# 14audio.net
KiCad netlist of a schematic drawn in Altium Designer
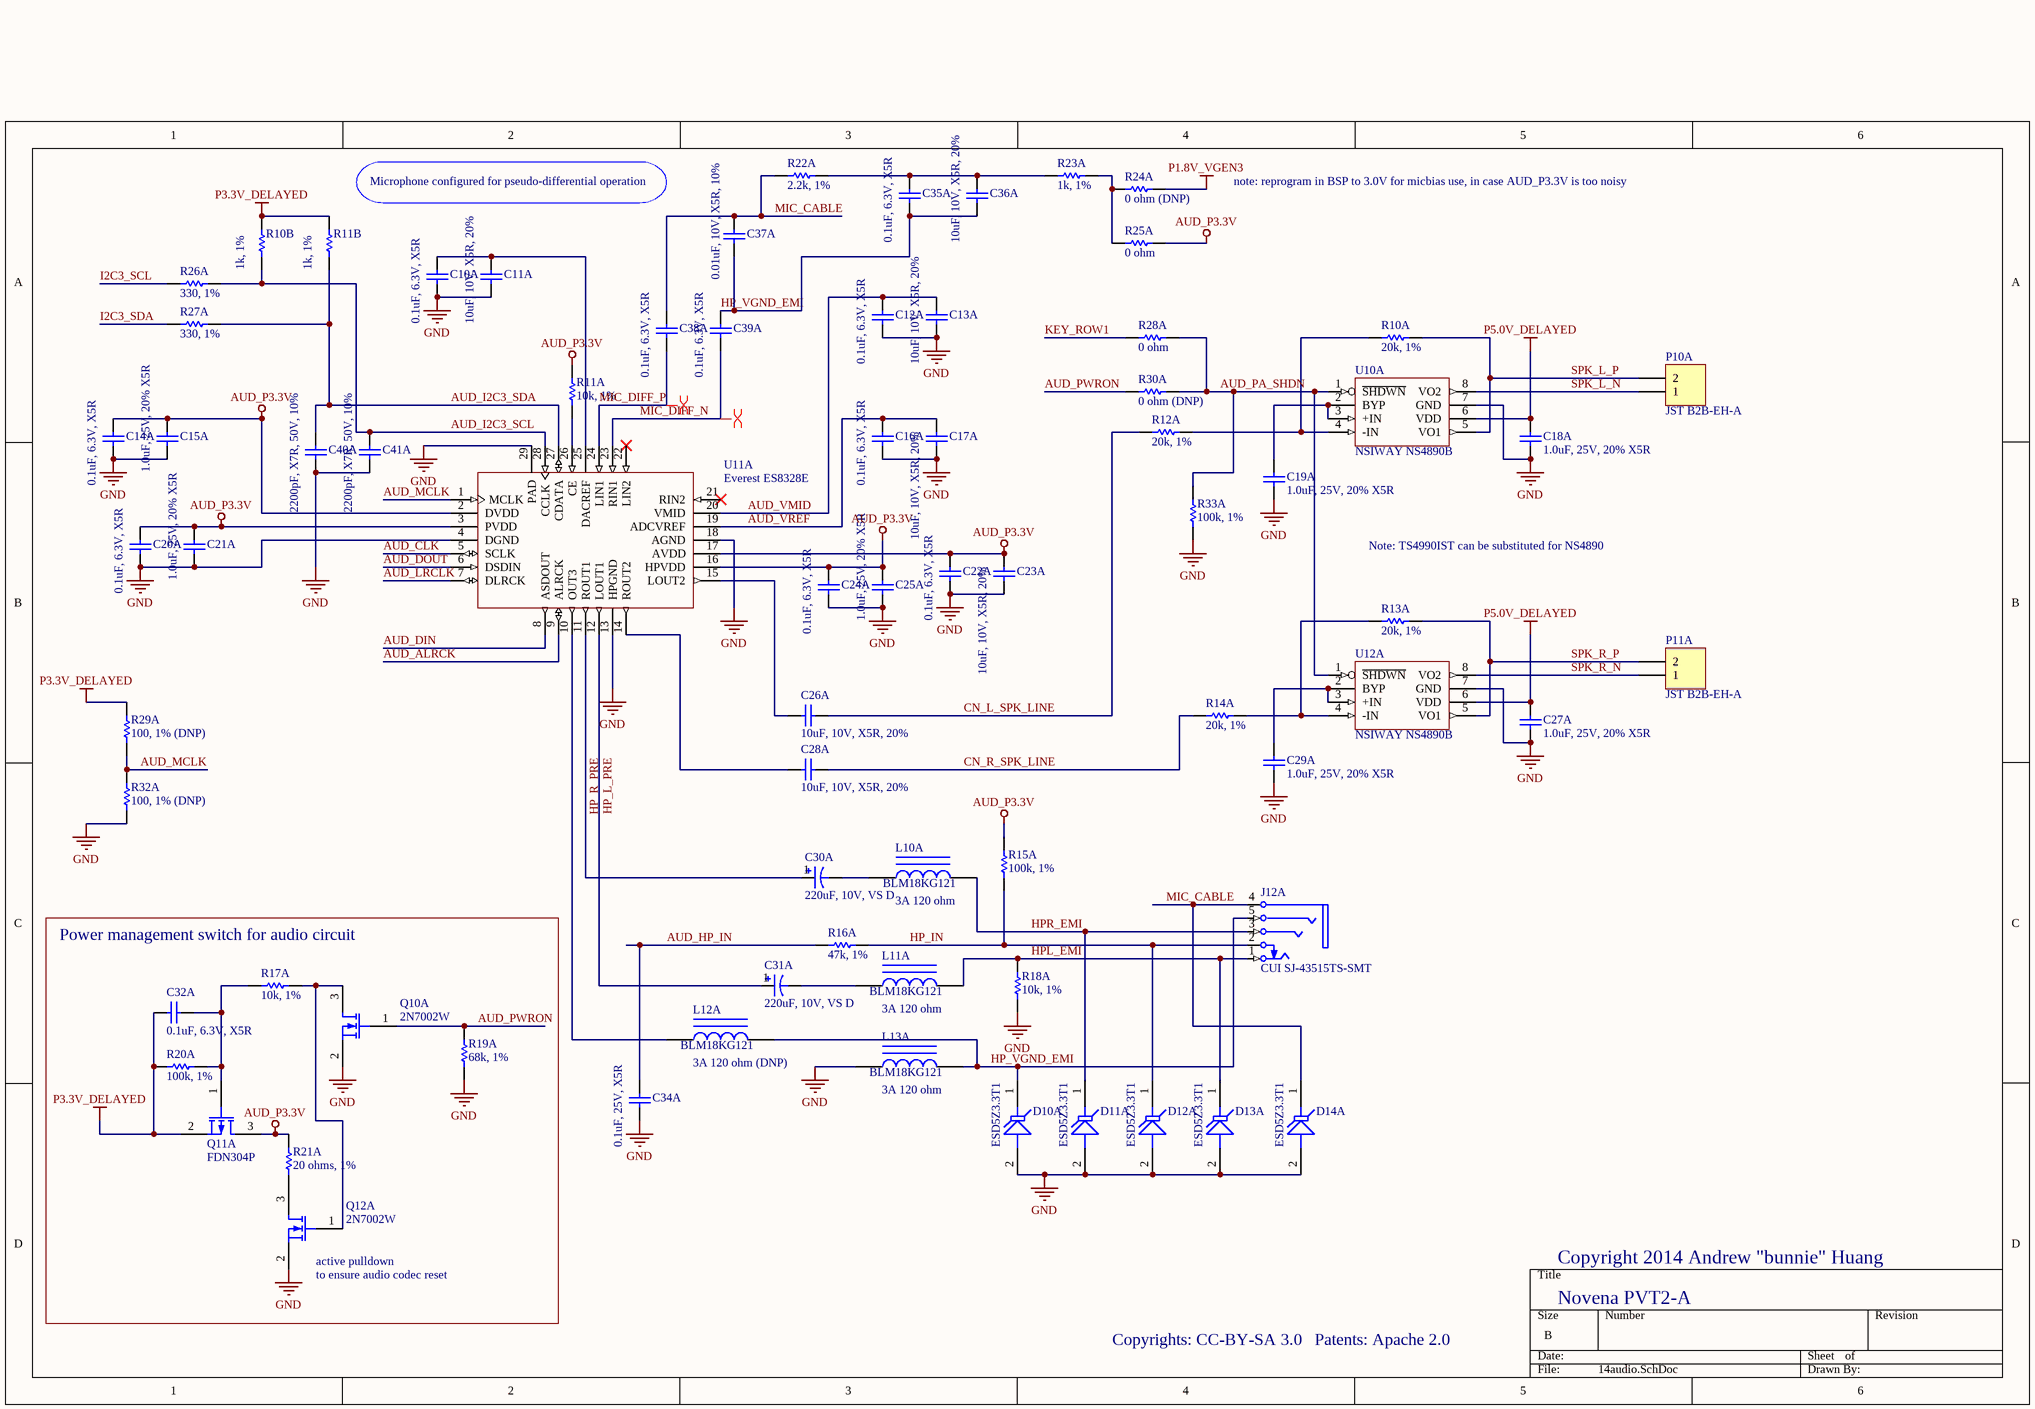
[diagram p0: 14audio.SchDoc]

(export (version "E")
  (design (tool "Eeschema 10.0.6"))
  (components
    (comp (ref "C10A")
      (value "0.1uF, 6.3V, X5R")
      (footprint "CAPC0603N_B")
      (description "Capacitor (Semiconductor SIM Model)")
      (fields (field (name "PUBLISHER") "Altium Limited"))
      (libsource (lib "Miscellaneous Devices") (part "Cap Semi"))
    )
    (comp (ref "C11A")
      (value "10uF, 10V, X5R, 20%")
      (footprint "CAPC1608N")
      (description "Capacitor (Semiconductor SIM Model)")
      (fields (field (name "PUBLISHER") "Altium Limited"))
      (libsource (lib "Miscellaneous Devices") (part "Cap Semi"))
    )
    (comp (ref "C12A")
      (value "0.1uF, 6.3V, X5R")
      (footprint "CAPC0603N_B")
      (description "Capacitor (Semiconductor SIM Model)")
      (fields (field (name "PUBLISHER") "Altium Limited"))
      (libsource (lib "Miscellaneous Devices") (part "Cap Semi"))
    )
    (comp (ref "C13A")
      (value "10uF, 10V, X5R, 20%")
      (footprint "CAPC1608N")
      (description "Capacitor (Semiconductor SIM Model)")
      (fields (field (name "PUBLISHER") "Altium Limited"))
      (libsource (lib "Miscellaneous Devices") (part "Cap Semi"))
    )
    (comp (ref "C14A")
      (value "0.1uF, 6.3V, X5R")
      (footprint "CAPC0603N_B")
      (description "Capacitor (Semiconductor SIM Model)")
      (fields (field (name "PUBLISHER") "Altium Limited"))
      (libsource (lib "Miscellaneous Devices") (part "Cap Semi"))
    )
    (comp (ref "C15A")
      (value "1.0uF, 25V, 20% X5R")
      (footprint "CAPC1608N")
      (description "Capacitor (Semiconductor SIM Model)")
      (fields (field (name "PUBLISHER") "Altium Limited"))
      (libsource (lib "Miscellaneous Devices") (part "Cap Semi"))
    )
    (comp (ref "C16A")
      (value "0.1uF, 6.3V, X5R")
      (footprint "CAPC0603N_B")
      (description "Capacitor (Semiconductor SIM Model)")
      (fields (field (name "PUBLISHER") "Altium Limited"))
      (libsource (lib "Miscellaneous Devices") (part "Cap Semi"))
    )
    (comp (ref "C17A")
      (value "10uF, 10V, X5R, 20%")
      (footprint "CAPC1608N")
      (description "Capacitor (Semiconductor SIM Model)")
      (fields (field (name "PUBLISHER") "Altium Limited"))
      (libsource (lib "Miscellaneous Devices") (part "Cap Semi"))
    )
    (comp (ref "C18A")
      (value "1.0uF, 25V, 20% X5R")
      (footprint "CAPC1608N")
      (description "Capacitor (Semiconductor SIM Model)")
      (fields (field (name "PUBLISHER") "Altium Limited"))
      (libsource (lib "Miscellaneous Devices") (part "Cap Semi"))
    )
    (comp (ref "C19A")
      (value "1.0uF, 25V, 20% X5R")
      (footprint "CAPC1608N")
      (description "Capacitor (Semiconductor SIM Model)")
      (fields (field (name "PUBLISHER") "Altium Limited"))
      (libsource (lib "Miscellaneous Devices") (part "Cap Semi"))
    )
    (comp (ref "C20A")
      (value "0.1uF, 6.3V, X5R")
      (footprint "CAPC0603N_B")
      (description "Capacitor (Semiconductor SIM Model)")
      (fields (field (name "PUBLISHER") "Altium Limited"))
      (libsource (lib "Miscellaneous Devices") (part "Cap Semi"))
    )
    (comp (ref "C21A")
      (value "1.0uF, 25V, 20% X5R")
      (footprint "CAPC1608N")
      (description "Capacitor (Semiconductor SIM Model)")
      (fields (field (name "PUBLISHER") "Altium Limited"))
      (libsource (lib "Miscellaneous Devices") (part "Cap Semi"))
    )
    (comp (ref "C22A")
      (value "0.1uF, 6.3V, X5R")
      (footprint "CAPC0603N_B")
      (description "Capacitor (Semiconductor SIM Model)")
      (fields (field (name "PUBLISHER") "Altium Limited"))
      (libsource (lib "Miscellaneous Devices") (part "Cap Semi"))
    )
    (comp (ref "C23A")
      (value "10uF, 10V, X5R, 20%")
      (footprint "CAPC1608N")
      (description "Capacitor (Semiconductor SIM Model)")
      (fields (field (name "PUBLISHER") "Altium Limited"))
      (libsource (lib "Miscellaneous Devices") (part "Cap Semi"))
    )
    (comp (ref "C24A")
      (value "0.1uF, 6.3V, X5R")
      (footprint "CAPC0603N_B")
      (description "Capacitor (Semiconductor SIM Model)")
      (fields (field (name "PUBLISHER") "Altium Limited"))
      (libsource (lib "Miscellaneous Devices") (part "Cap Semi"))
    )
    (comp (ref "C25A")
      (value "1.0uF, 25V, 20% X5R")
      (footprint "CAPC1608N")
      (description "Capacitor (Semiconductor SIM Model)")
      (fields (field (name "PUBLISHER") "Altium Limited"))
      (libsource (lib "Miscellaneous Devices") (part "Cap Semi"))
    )
    (comp (ref "C26A")
      (value "10uF, 10V, X5R, 20%")
      (footprint "CAPC1608N")
      (description "Capacitor (Semiconductor SIM Model)")
      (fields (field (name "PUBLISHER") "Altium Limited"))
      (libsource (lib "Miscellaneous Devices") (part "Cap Semi"))
    )
    (comp (ref "C27A")
      (value "1.0uF, 25V, 20% X5R")
      (footprint "CAPC1608N")
      (description "Capacitor (Semiconductor SIM Model)")
      (fields (field (name "PUBLISHER") "Altium Limited"))
      (libsource (lib "Miscellaneous Devices") (part "Cap Semi"))
    )
    (comp (ref "C28A")
      (value "10uF, 10V, X5R, 20%")
      (footprint "CAPC1608N")
      (description "Capacitor (Semiconductor SIM Model)")
      (fields (field (name "PUBLISHER") "Altium Limited"))
      (libsource (lib "Miscellaneous Devices") (part "Cap Semi"))
    )
    (comp (ref "C29A")
      (value "1.0uF, 25V, 20% X5R")
      (footprint "CAPC1608N")
      (description "Capacitor (Semiconductor SIM Model)")
      (fields (field (name "PUBLISHER") "Altium Limited"))
      (libsource (lib "Miscellaneous Devices") (part "Cap Semi"))
    )
    (comp (ref "C30A")
      (value "220uF, 10V, VS D")
      (footprint "6004pcb:ALCAP_D")
      (description "Polarized Capacitor (Surface Mount)")
      (fields (field (name "PUBLISHER") "Altium Limited"))
      (libsource (lib "Miscellaneous Devices") (part "Cap Pol3"))
    )
    (comp (ref "C31A")
      (value "220uF, 10V, VS D")
      (footprint "6004pcb:ALCAP_D")
      (description "Polarized Capacitor (Surface Mount)")
      (fields (field (name "PUBLISHER") "Altium Limited"))
      (libsource (lib "Miscellaneous Devices") (part "Cap Pol3"))
    )
    (comp (ref "C32A")
      (value "0.1uF, 6.3V, X5R")
      (footprint "CAPC0603N_B")
      (description "Capacitor (Semiconductor SIM Model)")
      (fields (field (name "PUBLISHER") "Altium Limited"))
      (libsource (lib "Miscellaneous Devices") (part "Cap Semi"))
    )
    (comp (ref "C34A")
      (value "0.1uF, 25V, X5R")
      (footprint "CAPC1005N")
      (description "Capacitor (Semiconductor SIM Model)")
      (fields (field (name "PUBLISHER") "Altium Limited"))
      (libsource (lib "Miscellaneous Devices") (part "Cap Semi"))
    )
    (comp (ref "C35A")
      (value "0.1uF, 6.3V, X5R")
      (footprint "CAPC0603N_B")
      (description "Capacitor (Semiconductor SIM Model)")
      (fields (field (name "PUBLISHER") "Altium Limited"))
      (libsource (lib "Miscellaneous Devices") (part "Cap Semi"))
    )
    (comp (ref "C36A")
      (value "10uF, 10V, X5R, 20%")
      (footprint "CAPC1608N")
      (description "Capacitor (Semiconductor SIM Model)")
      (fields (field (name "PUBLISHER") "Altium Limited"))
      (libsource (lib "Miscellaneous Devices") (part "Cap Semi"))
    )
    (comp (ref "C37A")
      (value "0.01uF, 10V, X5R, 10%")
      (footprint "CAPC0603N_B")
      (description "Capacitor (Semiconductor SIM Model)")
      (fields (field (name "PUBLISHER") "Altium Limited"))
      (libsource (lib "Miscellaneous Devices") (part "Cap Semi"))
    )
    (comp (ref "C38A")
      (value "0.1uF, 6.3V, X5R")
      (footprint "CAPC0603N_B")
      (description "Capacitor (Semiconductor SIM Model)")
      (fields (field (name "PUBLISHER") "Altium Limited"))
      (libsource (lib "Miscellaneous Devices") (part "Cap Semi"))
    )
    (comp (ref "C39A")
      (value "0.1uF, 6.3V, X5R")
      (footprint "CAPC0603N_B")
      (description "Capacitor (Semiconductor SIM Model)")
      (fields (field (name "PUBLISHER") "Altium Limited"))
      (libsource (lib "Miscellaneous Devices") (part "Cap Semi"))
    )
    (comp (ref "C40A")
      (value "2200pF, X7R, 50V, 10%")
      (footprint "CAPC1005N")
      (description "Capacitor (Semiconductor SIM Model)")
      (fields (field (name "PUBLISHER") "Altium Limited"))
      (libsource (lib "Miscellaneous Devices") (part "Cap Semi"))
    )
    (comp (ref "C41A")
      (value "2200pF, X7R, 50V, 10%")
      (footprint "CAPC1005N")
      (description "Capacitor (Semiconductor SIM Model)")
      (fields (field (name "PUBLISHER") "Altium Limited"))
      (libsource (lib "Miscellaneous Devices") (part "Cap Semi"))
    )
    (comp (ref "D10A")
      (value "ESD5Z3.3T1")
      (footprint "SOD-523")
      (description "On Semi 3.3V standoff TVS diode")
      (fields (field (name "PUBLISHER") "Altium Limited"))
      (libsource (lib "Miscellaneous Devices") (part "Tranzorb"))
    )
    (comp (ref "D11A")
      (value "ESD5Z3.3T1")
      (footprint "SOD-523")
      (description "On Semi 3.3V standoff TVS diode")
      (fields (field (name "PUBLISHER") "Altium Limited"))
      (libsource (lib "Miscellaneous Devices") (part "Tranzorb"))
    )
    (comp (ref "D12A")
      (value "ESD5Z3.3T1")
      (footprint "SOD-523")
      (description "On Semi 3.3V standoff TVS diode")
      (fields (field (name "PUBLISHER") "Altium Limited"))
      (libsource (lib "Miscellaneous Devices") (part "Tranzorb"))
    )
    (comp (ref "D13A")
      (value "ESD5Z3.3T1")
      (footprint "SOD-523")
      (description "On Semi 3.3V standoff TVS diode")
      (fields (field (name "PUBLISHER") "Altium Limited"))
      (libsource (lib "Miscellaneous Devices") (part "Tranzorb"))
    )
    (comp (ref "D14A")
      (value "ESD5Z3.3T1")
      (footprint "SOD-523")
      (description "On Semi 3.3V standoff TVS diode")
      (fields (field (name "PUBLISHER") "Altium Limited"))
      (libsource (lib "Miscellaneous Devices") (part "Tranzorb"))
    )
    (comp (ref "J12A")
      (value "CUI SJ-43515TS-SMT")
      (footprint "CUI_SJ_43515TS-SMT")
      (description "Jack Socket, 3.5mm, SMT, 4-conductor")
      (fields (field (name "PUBLISHER") "Altium Limited"))
      (libsource (lib "commonsch") (part "Phonejack4 TN"))
    )
    (comp (ref "L10A")
      (value "BLM18KG121")
      (footprint "INDC1608AN")
      (description "Magnetic-Core Inductor")
      (fields (field (name "ALTIUM_VALUE") "3A 120 ohm") (field (name "PUBLISHER") "Altium Limited"))
      (libsource (lib "Miscellaneous Devices") (part "Inductor Iron"))
    )
    (comp (ref "L11A")
      (value "BLM18KG121")
      (footprint "INDC1608AN")
      (description "Magnetic-Core Inductor")
      (fields (field (name "ALTIUM_VALUE") "3A 120 ohm") (field (name "PUBLISHER") "Altium Limited"))
      (libsource (lib "Miscellaneous Devices") (part "Inductor Iron"))
    )
    (comp (ref "L12A")
      (value "BLM18KG121")
      (footprint "INDC1608AN")
      (description "Magnetic-Core Inductor")
      (fields (field (name "ALTIUM_VALUE") "3A 120 ohm (DNP)") (field (name "PUBLISHER") "Altium Limited"))
      (libsource (lib "Miscellaneous Devices") (part "Inductor Iron"))
    )
    (comp (ref "L13A")
      (value "BLM18KG121")
      (footprint "INDC1608AN")
      (description "Magnetic-Core Inductor")
      (fields (field (name "ALTIUM_VALUE") "3A 120 ohm") (field (name "PUBLISHER") "Altium Limited"))
      (libsource (lib "Miscellaneous Devices") (part "Inductor Iron"))
    )
    (comp (ref "P10A")
      (value "JST B2B-EH-A")
      (footprint "JST_B2B_EH_A")
      (description "Header, 2-Pin")
      (fields (field (name "PUBLISHER") "Altium Limited"))
      (libsource (lib "Miscellaneous Connectors") (part "Header 2"))
    )
    (comp (ref "P11A")
      (value "JST B2B-EH-A")
      (footprint "JST_B2B_EH_A")
      (description "Header, 2-Pin")
      (fields (field (name "PUBLISHER") "Altium Limited"))
      (libsource (lib "Miscellaneous Connectors") (part "Header 2"))
    )
    (comp (ref "Q10A")
      (value "2N7002W")
      (footprint "SOT323-3AN")
      (description "N-Channel MOSFET")
      (fields (field (name "PUBLISHER") "Altium Limited"))
      (libsource (lib "Miscellaneous Devices") (part "MOSFET-N"))
    )
    (comp (ref "Q11A")
      (value "FDN304P")
      (footprint "SOT23-3N")
      (description "P-Channel MOSFET")
      (fields (field (name "PUBLISHER") "Altium Limited"))
      (libsource (lib "Miscellaneous Devices") (part "MOSFET-P"))
    )
    (comp (ref "Q12A")
      (value "2N7002W")
      (footprint "SOT323-3AN")
      (description "N-Channel MOSFET")
      (fields (field (name "PUBLISHER") "Altium Limited"))
      (libsource (lib "Miscellaneous Devices") (part "MOSFET-N"))
    )
    (comp (ref "R10A")
      (value "20k, 1%")
      (footprint "RESC1005N")
      (description "Resistor")
      (fields (field (name "PUBLISHER") "Altium Limited"))
      (libsource (lib "Miscellaneous Devices") (part "Res1"))
    )
    (comp (ref "R10B")
      (value "1k, 1%")
      (footprint "RESC1005N")
      (description "Resistor")
      (fields (field (name "PUBLISHER") "Altium Limited"))
      (libsource (lib "Miscellaneous Devices") (part "Res1"))
    )
    (comp (ref "R11A")
      (value "10k, 1%")
      (footprint "RESC1005N")
      (description "Resistor")
      (fields (field (name "PUBLISHER") "Altium Limited"))
      (libsource (lib "Miscellaneous Devices") (part "Res1"))
    )
    (comp (ref "R11B")
      (value "1k, 1%")
      (footprint "RESC1005N")
      (description "Resistor")
      (fields (field (name "PUBLISHER") "Altium Limited"))
      (libsource (lib "Miscellaneous Devices") (part "Res1"))
    )
    (comp (ref "R12A")
      (value "20k, 1%")
      (footprint "RESC1005N")
      (description "Resistor")
      (fields (field (name "PUBLISHER") "Altium Limited"))
      (libsource (lib "Miscellaneous Devices") (part "Res1"))
    )
    (comp (ref "R13A")
      (value "20k, 1%")
      (footprint "RESC1005N")
      (description "Resistor")
      (fields (field (name "PUBLISHER") "Altium Limited"))
      (libsource (lib "Miscellaneous Devices") (part "Res1"))
    )
    (comp (ref "R14A")
      (value "20k, 1%")
      (footprint "RESC1005N")
      (description "Resistor")
      (fields (field (name "PUBLISHER") "Altium Limited"))
      (libsource (lib "Miscellaneous Devices") (part "Res1"))
    )
    (comp (ref "R15A")
      (value "100k, 1%")
      (footprint "RESC1005N")
      (description "Resistor")
      (fields (field (name "PUBLISHER") "Altium Limited"))
      (libsource (lib "Miscellaneous Devices") (part "Res1"))
    )
    (comp (ref "R16A")
      (value "47k, 1%")
      (footprint "RESC1005N")
      (description "Resistor")
      (fields (field (name "PUBLISHER") "Altium Limited"))
      (libsource (lib "Miscellaneous Devices") (part "Res1"))
    )
    (comp (ref "R17A")
      (value "10k, 1%")
      (footprint "RESC1005N")
      (description "Resistor")
      (fields (field (name "PUBLISHER") "Altium Limited"))
      (libsource (lib "Miscellaneous Devices") (part "Res1"))
    )
    (comp (ref "R18A")
      (value "10k, 1%")
      (footprint "RESC1005N")
      (description "Resistor")
      (fields (field (name "PUBLISHER") "Altium Limited"))
      (libsource (lib "Miscellaneous Devices") (part "Res1"))
    )
    (comp (ref "R19A")
      (value "68k, 1%")
      (footprint "RESC1005N")
      (description "Resistor")
      (fields (field (name "PUBLISHER") "Altium Limited"))
      (libsource (lib "Miscellaneous Devices") (part "Res1"))
    )
    (comp (ref "R20A")
      (value "100k, 1%")
      (footprint "RESC1005N")
      (description "Resistor")
      (fields (field (name "PUBLISHER") "Altium Limited"))
      (libsource (lib "Miscellaneous Devices") (part "Res1"))
    )
    (comp (ref "R21A")
      (value "20 ohms, 1%")
      (footprint "RESC1005N")
      (description "Resistor")
      (fields (field (name "PUBLISHER") "Altium Limited"))
      (libsource (lib "Miscellaneous Devices") (part "Res1"))
    )
    (comp (ref "R22A")
      (value "2.2k, 1%")
      (footprint "RESC1005N")
      (description "Resistor")
      (fields (field (name "PUBLISHER") "Altium Limited"))
      (libsource (lib "Miscellaneous Devices") (part "Res1"))
    )
    (comp (ref "R23A")
      (value "1k, 1%")
      (footprint "RESC1005N")
      (description "Resistor")
      (fields (field (name "PUBLISHER") "Altium Limited"))
      (libsource (lib "Miscellaneous Devices") (part "Res1"))
    )
    (comp (ref "R24A")
      (value "0 ohm (DNP)")
      (footprint "RESC1005N")
      (description "Resistor")
      (fields (field (name "PUBLISHER") "Altium Limited"))
      (libsource (lib "Miscellaneous Devices") (part "Res1"))
    )
    (comp (ref "R25A")
      (value "0 ohm")
      (footprint "RESC1005N")
      (description "Resistor")
      (fields (field (name "PUBLISHER") "Altium Limited"))
      (libsource (lib "Miscellaneous Devices") (part "Res1"))
    )
    (comp (ref "R26A")
      (value "330, 1%")
      (footprint "RESC1005N")
      (description "Resistor")
      (fields (field (name "PUBLISHER") "Altium Limited"))
      (libsource (lib "Miscellaneous Devices") (part "Res1"))
    )
    (comp (ref "R27A")
      (value "330, 1%")
      (footprint "RESC1005N")
      (description "Resistor")
      (fields (field (name "PUBLISHER") "Altium Limited"))
      (libsource (lib "Miscellaneous Devices") (part "Res1"))
    )
    (comp (ref "R28A")
      (value "0 ohm")
      (footprint "RESC1005N")
      (description "Resistor")
      (fields (field (name "PUBLISHER") "Altium Limited"))
      (libsource (lib "Miscellaneous Devices") (part "Res1"))
    )
    (comp (ref "R29A")
      (value "100, 1% (DNP)")
      (footprint "RESC1005N")
      (description "Resistor")
      (fields (field (name "PUBLISHER") "Altium Limited"))
      (libsource (lib "Miscellaneous Devices") (part "Res1"))
    )
    (comp (ref "R30A")
      (value "0 ohm (DNP)")
      (footprint "RESC1005N")
      (description "Resistor")
      (fields (field (name "PUBLISHER") "Altium Limited"))
      (libsource (lib "Miscellaneous Devices") (part "Res1"))
    )
    (comp (ref "R32A")
      (value "100, 1% (DNP)")
      (footprint "RESC1005N")
      (description "Resistor")
      (fields (field (name "PUBLISHER") "Altium Limited"))
      (libsource (lib "Miscellaneous Devices") (part "Res1"))
    )
    (comp (ref "R33A")
      (value "100k, 1%")
      (footprint "RESC1005N")
      (description "Resistor")
      (fields (field (name "PUBLISHER") "Altium Limited"))
      (libsource (lib "Miscellaneous Devices") (part "Res1"))
    )
    (comp (ref "U10A")
      (value "NSIWAY NS4890B")
      (footprint "MSOP8")
      (description "1W 8 ohm low-cost amplifier")
      (libsource (lib "commonsch") (part "NSIWAY_NS4890"))
    )
    (comp (ref "U11A")
      (value "Everest ES8328E")
      (footprint "QFN50P500X500-28V1N")
      (description "Low-cost audio CODEC by Everest")
      (libsource (lib "commonsch") (part "Everest_ES8328"))
    )
    (comp (ref "U12A")
      (value "NSIWAY NS4890B")
      (footprint "MSOP8")
      (description "1W 8 ohm low-cost amplifier")
      (libsource (lib "commonsch") (part "NSIWAY_NS4890"))
    )
  )
  (nets
    (net (code "1") (name "/AUD_ALRCK") (class "Default")
      (node (ref "U11A") (pin "9") (pinfunction "ALRCK_9") (pintype "bidirectional"))
    )
    (net (code "2") (name "/AUD_CLK") (class "Default")
      (node (ref "U11A") (pin "5") (pinfunction "SCLK_5") (pintype "bidirectional"))
    )
    (net (code "3") (name "/AUD_DIN") (class "Default")
      (node (ref "U11A") (pin "8") (pinfunction "ASDOUT_8") (pintype "output"))
    )
    (net (code "4") (name "/AUD_DOUT") (class "Default")
      (node (ref "U11A") (pin "6") (pinfunction "DSDIN_6") (pintype "input"))
    )
    (net (code "5") (name "/AUD_HP_IN") (class "Default")
      (node (ref "C34A") (pin "2") (pinfunction "2_2") (pintype "passive"))
      (node (ref "R16A") (pin "2") (pinfunction "2_2") (pintype "passive"))
    )
    (net (code "6") (name "/AUD_I2C3_SCL") (class "Default")
      (node (ref "C41A") (pin "2") (pinfunction "2_2") (pintype "passive"))
      (node (ref "R10B") (pin "1") (pinfunction "1_1") (pintype "passive"))
      (node (ref "R26A") (pin "1") (pinfunction "1_1") (pintype "passive"))
      (node (ref "U11A") (pin "28") (pinfunction "CCLK_28") (pintype "input"))
    )
    (net (code "7") (name "/AUD_I2C3_SDA") (class "Default")
      (node (ref "C40A") (pin "2") (pinfunction "2_2") (pintype "passive"))
      (node (ref "R11B") (pin "1") (pinfunction "1_1") (pintype "passive"))
      (node (ref "R27A") (pin "1") (pinfunction "1_1") (pintype "passive"))
      (node (ref "U11A") (pin "27") (pinfunction "CDATA_27") (pintype "bidirectional"))
    )
    (net (code "8") (name "/AUD_LRCLK") (class "Default")
      (node (ref "U11A") (pin "7") (pinfunction "DLRCK_7") (pintype "bidirectional"))
    )
    (net (code "9") (name "/AUD_MCLK") (class "Default")
      (node (ref "R29A") (pin "1") (pinfunction "1_1") (pintype "passive"))
      (node (ref "R32A") (pin "2") (pinfunction "2_2") (pintype "passive"))
      (node (ref "U11A") (pin "1") (pinfunction "MCLK_1") (pintype "input"))
    )
    (net (code "10") (name "/AUD_PA_SHDN") (class "Default")
      (node (ref "R28A") (pin "2") (pinfunction "2_2") (pintype "passive"))
      (node (ref "R30A") (pin "2") (pinfunction "2_2") (pintype "passive"))
      (node (ref "R33A") (pin "2") (pinfunction "2_2") (pintype "passive"))
      (node (ref "U10A") (pin "1") (pinfunction "~{SHDWN}_1") (pintype "input"))
      (node (ref "U12A") (pin "1") (pinfunction "~{SHDWN}_1") (pintype "input"))
    )
    (net (code "11") (name "/AUD_PWRON") (class "Default")
      (node (ref "Q10A") (pin "1") (pinfunction "G_1") (pintype "passive"))
      (node (ref "R19A") (pin "1") (pinfunction "1_1") (pintype "passive"))
      (node (ref "R30A") (pin "1") (pinfunction "1_1") (pintype "passive"))
    )
    (net (code "12") (name "/AUD_VMID") (class "Default")
      (node (ref "C12A") (pin "2") (pinfunction "2_2") (pintype "passive"))
      (node (ref "C13A") (pin "1") (pinfunction "1_1") (pintype "passive"))
      (node (ref "U11A") (pin "20") (pinfunction "VMID_20") (pintype "passive"))
    )
    (net (code "13") (name "/AUD_VREF") (class "Default")
      (node (ref "C16A") (pin "2") (pinfunction "2_2") (pintype "passive"))
      (node (ref "C17A") (pin "1") (pinfunction "1_1") (pintype "passive"))
      (node (ref "U11A") (pin "19") (pinfunction "ADCVREF_19") (pintype "passive"))
    )
    (net (code "14") (name "/CN_L_SPK_LINE") (class "Default")
      (node (ref "C26A") (pin "2") (pinfunction "2_2") (pintype "passive"))
      (node (ref "R12A") (pin "2") (pinfunction "2_2") (pintype "passive"))
    )
    (net (code "15") (name "/CN_R_SPK_LINE") (class "Default")
      (node (ref "C28A") (pin "2") (pinfunction "2_2") (pintype "passive"))
      (node (ref "R14A") (pin "2") (pinfunction "2_2") (pintype "passive"))
    )
    (net (code "16") (name "/HPL_EMI") (class "Default")
      (node (ref "D13A") (pin "1") (pinfunction "K_1") (pintype "passive"))
      (node (ref "J12A") (pin "1") (pinfunction "T_1") (pintype "input"))
      (node (ref "L11A") (pin "2") (pinfunction "2_2") (pintype "passive"))
      (node (ref "R18A") (pin "1") (pinfunction "1_1") (pintype "passive"))
    )
    (net (code "17") (name "/HPR_EMI") (class "Default")
      (node (ref "D11A") (pin "1") (pinfunction "K_1") (pintype "passive"))
      (node (ref "J12A") (pin "3") (pinfunction "R_3") (pintype "input"))
      (node (ref "L10A") (pin "2") (pinfunction "2_2") (pintype "passive"))
    )
    (net (code "18") (name "/HP_IN") (class "Default")
      (node (ref "D12A") (pin "1") (pinfunction "K_1") (pintype "passive"))
      (node (ref "J12A") (pin "2") (pinfunction "TN_2") (pintype "passive"))
      (node (ref "R15A") (pin "1") (pinfunction "1_1") (pintype "passive"))
      (node (ref "R16A") (pin "1") (pinfunction "1_1") (pintype "passive"))
    )
    (net (code "19") (name "/HP_L_PRE") (class "Default")
      (node (ref "C31A") (pin "1") (pinfunction "1_1") (pintype "passive"))
      (node (ref "U11A") (pin "12") (pinfunction "LOUT1_12") (pintype "output"))
    )
    (net (code "20") (name "/HP_R_PRE") (class "Default")
      (node (ref "C30A") (pin "1") (pinfunction "1_1") (pintype "passive"))
      (node (ref "U11A") (pin "11") (pinfunction "ROUT1_11") (pintype "output"))
    )
    (net (code "21") (name "/HP_VGND_EMI") (class "Default")
      (node (ref "C35A") (pin "1") (pinfunction "1_1") (pintype "passive"))
      (node (ref "C36A") (pin "2") (pinfunction "2_2") (pintype "passive"))
      (node (ref "C37A") (pin "2") (pinfunction "2_2") (pintype "passive"))
      (node (ref "C39A") (pin "2") (pinfunction "2_2") (pintype "passive"))
      (node (ref "D10A") (pin "1") (pinfunction "K_1") (pintype "passive"))
      (node (ref "J12A") (pin "5") (pinfunction "R_5") (pintype "input"))
      (node (ref "L12A") (pin "2") (pinfunction "2_2") (pintype "passive"))
      (node (ref "L13A") (pin "2") (pinfunction "2_2") (pintype "passive"))
    )
    (net (code "22") (name "/I2C3_SCL") (class "Default")
      (node (ref "R26A") (pin "2") (pinfunction "2_2") (pintype "passive"))
    )
    (net (code "23") (name "/I2C3_SDA") (class "Default")
      (node (ref "R27A") (pin "2") (pinfunction "2_2") (pintype "passive"))
    )
    (net (code "24") (name "/KEY_ROW1") (class "Default")
      (node (ref "R28A") (pin "1") (pinfunction "1_1") (pintype "passive"))
    )
    (net (code "25") (name "/MIC_CABLE") (class "Default")
      (node (ref "C37A") (pin "1") (pinfunction "1_1") (pintype "passive"))
      (node (ref "C38A") (pin "2") (pinfunction "2_2") (pintype "passive"))
      (node (ref "D14A") (pin "1") (pinfunction "K_1") (pintype "passive"))
      (node (ref "J12A") (pin "4") (pinfunction "S_4") (pintype "power_in"))
      (node (ref "R22A") (pin "1") (pinfunction "1_1") (pintype "passive"))
    )
    (net (code "26") (name "/MIC_DIFF_N") (class "Default")
      (node (ref "C39A") (pin "1") (pinfunction "1_1") (pintype "passive"))
      (node (ref "U11A") (pin "23") (pinfunction "RIN1_23") (pintype "input"))
    )
    (net (code "27") (name "/MIC_DIFF_P") (class "Default")
      (node (ref "C38A") (pin "1") (pinfunction "1_1") (pintype "passive"))
      (node (ref "U11A") (pin "24") (pinfunction "LIN1_24") (pintype "input"))
    )
    (net (code "28") (name "/SPK_L_N") (class "Default")
      (node (ref "P10A") (pin "1") (pinfunction "1_1") (pintype "passive"))
      (node (ref "U10A") (pin "8") (pinfunction "VO2_8") (pintype "output"))
    )
    (net (code "29") (name "/SPK_L_P") (class "Default")
      (node (ref "P10A") (pin "2") (pinfunction "2_2") (pintype "passive"))
      (node (ref "R10A") (pin "1") (pinfunction "1_1") (pintype "passive"))
      (node (ref "U10A") (pin "5") (pinfunction "VO1_5") (pintype "output"))
    )
    (net (code "30") (name "/SPK_R_N") (class "Default")
      (node (ref "P11A") (pin "1") (pinfunction "1_1") (pintype "passive"))
      (node (ref "U12A") (pin "8") (pinfunction "VO2_8") (pintype "output"))
    )
    (net (code "31") (name "/SPK_R_P") (class "Default")
      (node (ref "P11A") (pin "2") (pinfunction "2_2") (pintype "passive"))
      (node (ref "R13A") (pin "1") (pinfunction "1_1") (pintype "passive"))
      (node (ref "U12A") (pin "5") (pinfunction "VO1_5") (pintype "output"))
    )
    (net (code "32") (name "AUD_P3.3V") (class "Default")
      (node (ref "C14A") (pin "2") (pinfunction "2_2") (pintype "passive"))
      (node (ref "C15A") (pin "2") (pinfunction "2_2") (pintype "passive"))
      (node (ref "C20A") (pin "2") (pinfunction "2_2") (pintype "passive"))
      (node (ref "C21A") (pin "2") (pinfunction "2_2") (pintype "passive"))
      (node (ref "C22A") (pin "2") (pinfunction "2_2") (pintype "passive"))
      (node (ref "C23A") (pin "1") (pinfunction "1_1") (pintype "passive"))
      (node (ref "C24A") (pin "2") (pinfunction "2_2") (pintype "passive"))
      (node (ref "C25A") (pin "2") (pinfunction "2_2") (pintype "passive"))
      (node (ref "Q11A") (pin "3") (pinfunction "D_3") (pintype "passive"))
      (node (ref "R11A") (pin "2") (pinfunction "2_2") (pintype "passive"))
      (node (ref "R15A") (pin "2") (pinfunction "2_2") (pintype "passive"))
      (node (ref "R21A") (pin "1") (pinfunction "1_1") (pintype "passive"))
      (node (ref "R25A") (pin "2") (pinfunction "2_2") (pintype "passive"))
      (node (ref "U11A") (pin "16") (pinfunction "HPVDD_16") (pintype "power_in"))
      (node (ref "U11A") (pin "17") (pinfunction "AVDD_17") (pintype "power_in"))
      (node (ref "U11A") (pin "2") (pinfunction "DVDD_2") (pintype "power_in"))
      (node (ref "U11A") (pin "3") (pinfunction "PVDD_3") (pintype "power_in"))
    )
    (net (code "33") (name "GND") (class "Default")
      (node (ref "C10A") (pin "1") (pinfunction "1_1") (pintype "passive"))
      (node (ref "C11A") (pin "2") (pinfunction "2_2") (pintype "passive"))
      (node (ref "C12A") (pin "1") (pinfunction "1_1") (pintype "passive"))
      (node (ref "C13A") (pin "2") (pinfunction "2_2") (pintype "passive"))
      (node (ref "C14A") (pin "1") (pinfunction "1_1") (pintype "passive"))
      (node (ref "C15A") (pin "1") (pinfunction "1_1") (pintype "passive"))
      (node (ref "C16A") (pin "1") (pinfunction "1_1") (pintype "passive"))
      (node (ref "C17A") (pin "2") (pinfunction "2_2") (pintype "passive"))
      (node (ref "C18A") (pin "1") (pinfunction "1_1") (pintype "passive"))
      (node (ref "C19A") (pin "1") (pinfunction "1_1") (pintype "passive"))
      (node (ref "C20A") (pin "1") (pinfunction "1_1") (pintype "passive"))
      (node (ref "C21A") (pin "1") (pinfunction "1_1") (pintype "passive"))
      (node (ref "C22A") (pin "1") (pinfunction "1_1") (pintype "passive"))
      (node (ref "C23A") (pin "2") (pinfunction "2_2") (pintype "passive"))
      (node (ref "C24A") (pin "1") (pinfunction "1_1") (pintype "passive"))
      (node (ref "C25A") (pin "1") (pinfunction "1_1") (pintype "passive"))
      (node (ref "C27A") (pin "1") (pinfunction "1_1") (pintype "passive"))
      (node (ref "C29A") (pin "1") (pinfunction "1_1") (pintype "passive"))
      (node (ref "C34A") (pin "1") (pinfunction "1_1") (pintype "passive"))
      (node (ref "C40A") (pin "1") (pinfunction "1_1") (pintype "passive"))
      (node (ref "C41A") (pin "1") (pinfunction "1_1") (pintype "passive"))
      (node (ref "D10A") (pin "2") (pinfunction "A_2") (pintype "passive"))
      (node (ref "D11A") (pin "2") (pinfunction "A_2") (pintype "passive"))
      (node (ref "D12A") (pin "2") (pinfunction "A_2") (pintype "passive"))
      (node (ref "D13A") (pin "2") (pinfunction "A_2") (pintype "passive"))
      (node (ref "D14A") (pin "2") (pinfunction "A_2") (pintype "passive"))
      (node (ref "L13A") (pin "1") (pinfunction "1_1") (pintype "passive"))
      (node (ref "Q10A") (pin "2") (pinfunction "S_2") (pintype "passive"))
      (node (ref "Q12A") (pin "2") (pinfunction "S_2") (pintype "passive"))
      (node (ref "R18A") (pin "2") (pinfunction "2_2") (pintype "passive"))
      (node (ref "R19A") (pin "2") (pinfunction "2_2") (pintype "passive"))
      (node (ref "R32A") (pin "1") (pinfunction "1_1") (pintype "passive"))
      (node (ref "R33A") (pin "1") (pinfunction "1_1") (pintype "passive"))
      (node (ref "U10A") (pin "7") (pinfunction "GND_7") (pintype "power_in"))
      (node (ref "U11A") (pin "13") (pinfunction "HPGND_13") (pintype "power_in"))
      (node (ref "U11A") (pin "18") (pinfunction "AGND_18") (pintype "power_in"))
      (node (ref "U11A") (pin "29") (pinfunction "PAD_29") (pintype "passive"))
      (node (ref "U11A") (pin "4") (pinfunction "DGND_4") (pintype "power_in"))
      (node (ref "U12A") (pin "7") (pinfunction "GND_7") (pintype "power_in"))
    )
    (net (code "34") (name "Net-(C30A-Pad2)") (class "Default")
      (node (ref "C30A") (pin "2") (pinfunction "2_2") (pintype "passive"))
      (node (ref "L10A") (pin "1") (pinfunction "1_1") (pintype "passive"))
    )
    (net (code "35") (name "Net-(C31A-Pad2)") (class "Default")
      (node (ref "C31A") (pin "2") (pinfunction "2_2") (pintype "passive"))
      (node (ref "L11A") (pin "1") (pinfunction "1_1") (pintype "passive"))
    )
    (net (code "36") (name "Net-(C35A-Pad2)") (class "Default")
      (node (ref "C35A") (pin "2") (pinfunction "2_2") (pintype "passive"))
      (node (ref "C36A") (pin "1") (pinfunction "1_1") (pintype "passive"))
      (node (ref "R22A") (pin "2") (pinfunction "2_2") (pintype "passive"))
      (node (ref "R23A") (pin "1") (pinfunction "1_1") (pintype "passive"))
    )
    (net (code "37") (name "Net-(Q10A-D)") (class "Default")
      (node (ref "Q10A") (pin "3") (pinfunction "D_3") (pintype "passive"))
      (node (ref "Q12A") (pin "1") (pinfunction "G_1") (pintype "passive"))
      (node (ref "R17A") (pin "2") (pinfunction "2_2") (pintype "passive"))
    )
    (net (code "38") (name "Net-(Q11A-G)") (class "Default")
      (node (ref "C32A") (pin "1") (pinfunction "1_1") (pintype "passive"))
      (node (ref "Q11A") (pin "1") (pinfunction "G_1") (pintype "passive"))
      (node (ref "R17A") (pin "1") (pinfunction "1_1") (pintype "passive"))
      (node (ref "R20A") (pin "1") (pinfunction "1_1") (pintype "passive"))
    )
    (net (code "39") (name "Net-(Q12A-D)") (class "Default")
      (node (ref "Q12A") (pin "3") (pinfunction "D_3") (pintype "passive"))
      (node (ref "R21A") (pin "2") (pinfunction "2_2") (pintype "passive"))
    )
    (net (code "40") (name "Net-(R23A-Pad2)") (class "Default")
      (node (ref "R23A") (pin "2") (pinfunction "2_2") (pintype "passive"))
      (node (ref "R24A") (pin "1") (pinfunction "1_1") (pintype "passive"))
      (node (ref "R25A") (pin "1") (pinfunction "1_1") (pintype "passive"))
    )
    (net (code "41") (name "Net-(U10A-+IN)") (class "Default")
      (node (ref "C19A") (pin "2") (pinfunction "2_2") (pintype "passive"))
      (node (ref "U10A") (pin "2") (pinfunction "BYP_2") (pintype "passive"))
      (node (ref "U10A") (pin "3") (pinfunction "+IN_3") (pintype "input"))
    )
    (net (code "42") (name "Net-(U10A--IN)") (class "Default")
      (node (ref "R10A") (pin "2") (pinfunction "2_2") (pintype "passive"))
      (node (ref "R12A") (pin "1") (pinfunction "1_1") (pintype "passive"))
      (node (ref "U10A") (pin "4") (pinfunction "-IN_4") (pintype "input"))
    )
    (net (code "43") (name "Net-(U11A-CE)") (class "Default")
      (node (ref "R11A") (pin "1") (pinfunction "1_1") (pintype "passive"))
      (node (ref "U11A") (pin "26") (pinfunction "CE_26") (pintype "input"))
    )
    (net (code "44") (name "Net-(U11A-DACREF)") (class "Default")
      (node (ref "C10A") (pin "2") (pinfunction "2_2") (pintype "passive"))
      (node (ref "C11A") (pin "1") (pinfunction "1_1") (pintype "passive"))
      (node (ref "U11A") (pin "25") (pinfunction "DACREF_25") (pintype "passive"))
    )
    (net (code "45") (name "Net-(U11A-LOUT2)") (class "Default")
      (node (ref "C26A") (pin "1") (pinfunction "1_1") (pintype "passive"))
      (node (ref "U11A") (pin "15") (pinfunction "LOUT2_15") (pintype "output"))
    )
    (net (code "46") (name "Net-(U11A-OUT3)") (class "Default")
      (node (ref "L12A") (pin "1") (pinfunction "1_1") (pintype "passive"))
      (node (ref "U11A") (pin "10") (pinfunction "OUT3_10") (pintype "output"))
    )
    (net (code "47") (name "Net-(U11A-ROUT2)") (class "Default")
      (node (ref "C28A") (pin "1") (pinfunction "1_1") (pintype "passive"))
      (node (ref "U11A") (pin "14") (pinfunction "ROUT2_14") (pintype "output"))
    )
    (net (code "48") (name "Net-(U12A-+IN)") (class "Default")
      (node (ref "C29A") (pin "2") (pinfunction "2_2") (pintype "passive"))
      (node (ref "U12A") (pin "2") (pinfunction "BYP_2") (pintype "passive"))
      (node (ref "U12A") (pin "3") (pinfunction "+IN_3") (pintype "input"))
    )
    (net (code "49") (name "Net-(U12A--IN)") (class "Default")
      (node (ref "R13A") (pin "2") (pinfunction "2_2") (pintype "passive"))
      (node (ref "R14A") (pin "1") (pinfunction "1_1") (pintype "passive"))
      (node (ref "U12A") (pin "4") (pinfunction "-IN_4") (pintype "input"))
    )
    (net (code "50") (name "P1.8V_VGEN3") (class "Default")
      (node (ref "R24A") (pin "2") (pinfunction "2_2") (pintype "passive"))
    )
    (net (code "51") (name "P3.3V_DELAYED") (class "Default")
      (node (ref "C32A") (pin "2") (pinfunction "2_2") (pintype "passive"))
      (node (ref "Q11A") (pin "2") (pinfunction "S_2") (pintype "passive"))
      (node (ref "R10B") (pin "2") (pinfunction "2_2") (pintype "passive"))
      (node (ref "R11B") (pin "2") (pinfunction "2_2") (pintype "passive"))
      (node (ref "R20A") (pin "2") (pinfunction "2_2") (pintype "passive"))
      (node (ref "R29A") (pin "2") (pinfunction "2_2") (pintype "passive"))
    )
    (net (code "52") (name "P5.0V_DELAYED") (class "Default")
      (node (ref "C18A") (pin "2") (pinfunction "2_2") (pintype "passive"))
      (node (ref "C27A") (pin "2") (pinfunction "2_2") (pintype "passive"))
      (node (ref "U10A") (pin "6") (pinfunction "VDD_6") (pintype "power_in"))
      (node (ref "U12A") (pin "6") (pinfunction "VDD_6") (pintype "power_in"))
    )
    (net (code "53") (name "unconnected-(U11A-LIN2-Pad22)") (class "Default")
      (node (ref "U11A") (pin "22") (pinfunction "LIN2_22") (pintype "input+no_connect"))
    )
    (net (code "54") (name "unconnected-(U11A-RIN2-Pad21)") (class "Default")
      (node (ref "U11A") (pin "21") (pinfunction "RIN2_21") (pintype "input+no_connect"))
    )
  )
)
